# GA1A1S202WP-REV-B.net
KiCad netlist of a schematic drawn in EAGLE
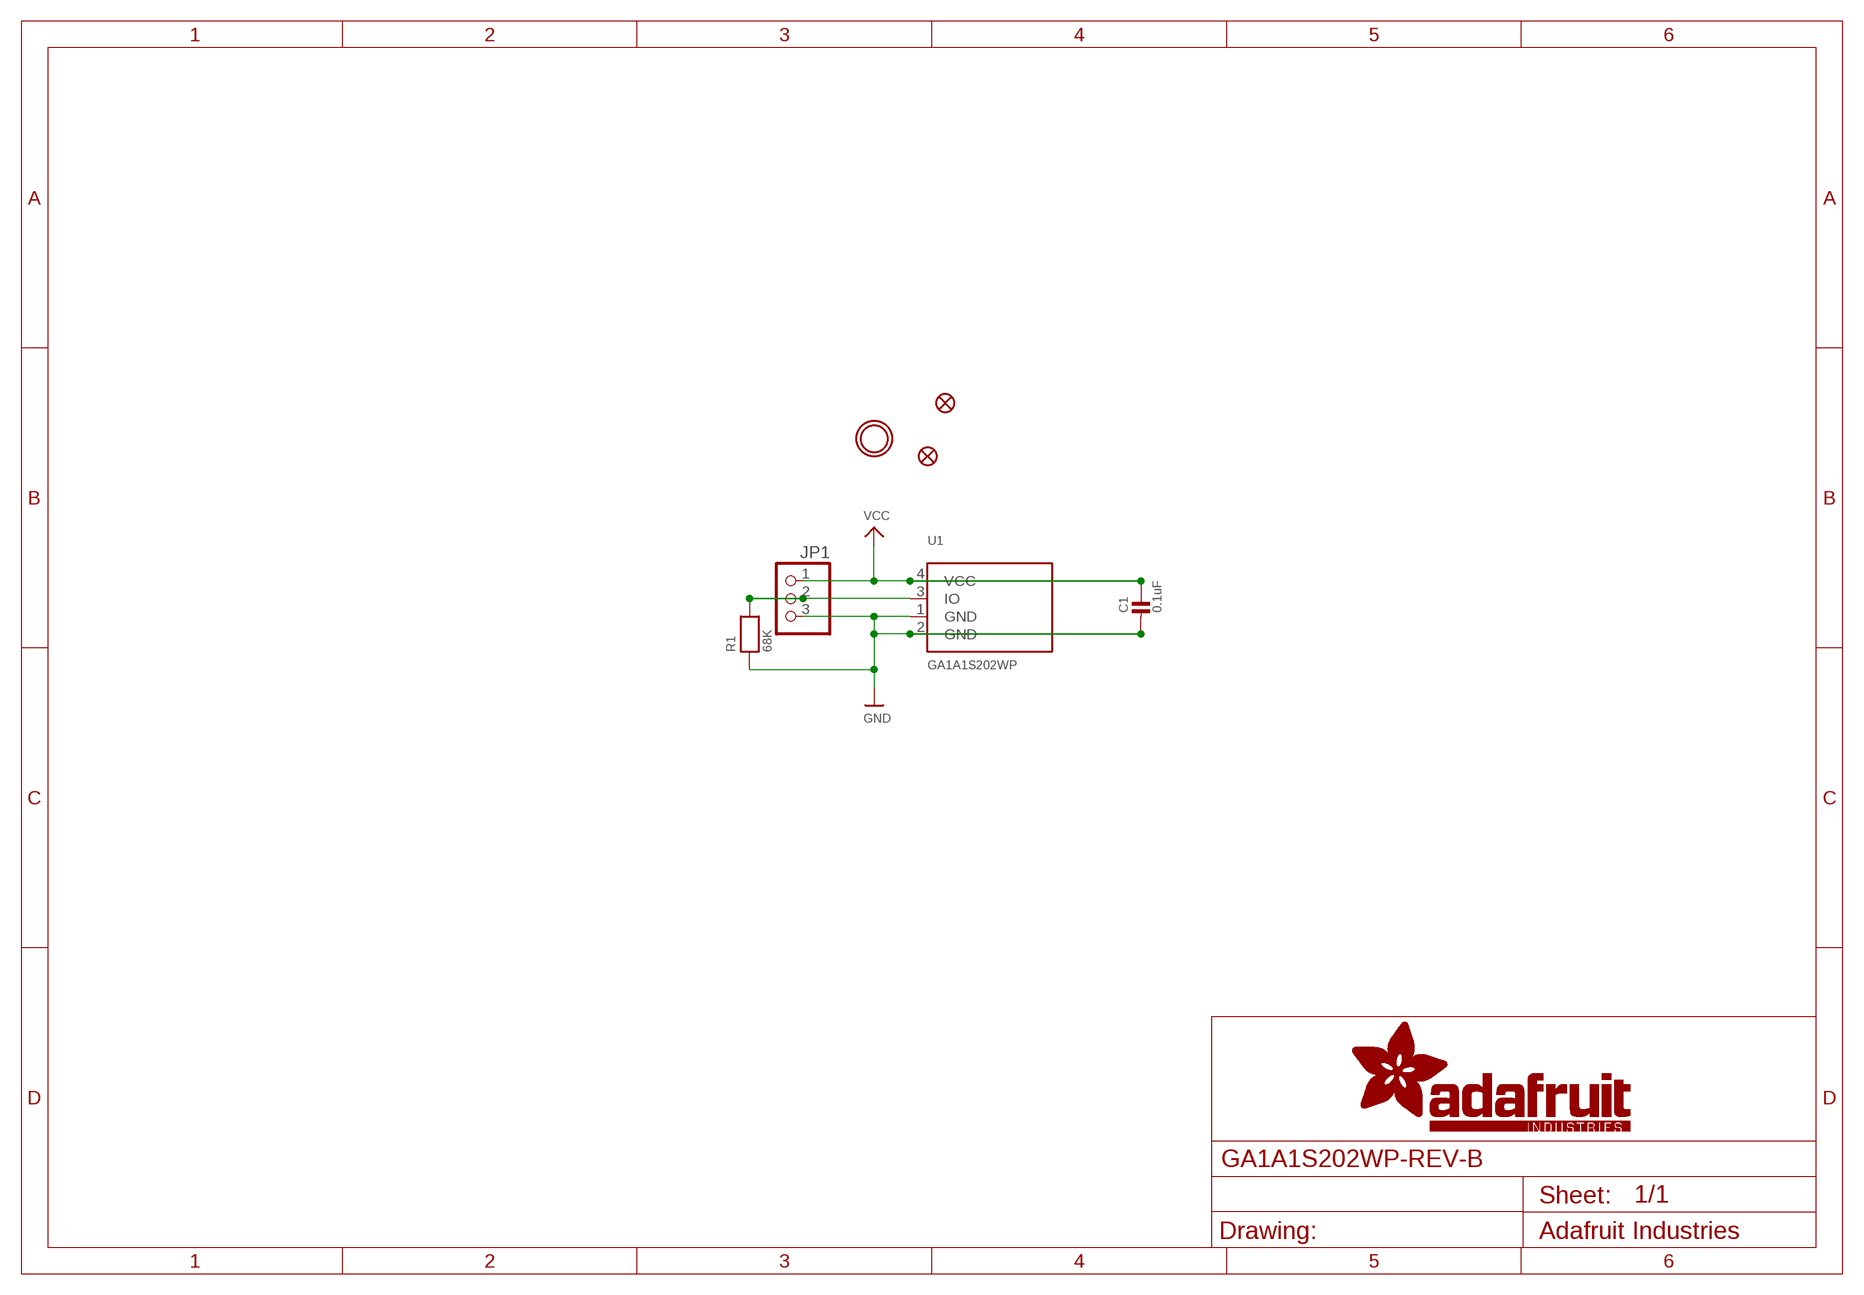
[diagram p0: schematic, sheet 1]

(export (version "E")
  (design (tool "Eeschema 10.0.6"))
  (components
    (comp (ref "C1")
      (value "0.1uF")
      (footprint "eagle-import:_0805MP")
      (libsource (lib "eagle-import") (part "CAP_CERAMIC_0805MP"))
    )
    (comp (ref "FID1")
      (value "FIDUCIAL\"\"")
      (footprint "eagle-import:FIDUCIAL_1MM")
      (libsource (lib "eagle-import") (part "FIDUCIAL{dblquote}{dblquote}"))
    )
    (comp (ref "FID2")
      (value "FIDUCIAL\"\"")
      (footprint "eagle-import:FIDUCIAL_1MM")
      (libsource (lib "eagle-import") (part "FIDUCIAL{dblquote}{dblquote}"))
    )
    (comp (ref "JP1")
      (value "HEADER-1X3ROUND")
      (footprint "eagle-import:1X03_ROUND")
      (libsource (lib "eagle-import") (part "HEADER-1X3ROUND"))
    )
    (comp (ref "R1")
      (value "68K")
      (footprint "eagle-import:_0805MP")
      (libsource (lib "eagle-import") (part "RESISTOR_0805MP"))
    )
    (comp (ref "U$3")
      (value "MOUNTINGHOLE2.5")
      (footprint "eagle-import:MOUNTINGHOLE_2.5_PLATED")
      (libsource (lib "eagle-import") (part "MOUNTINGHOLE2.5"))
    )
    (comp (ref "U1")
      (value "GA1A1S202WP")
      (footprint "eagle-import:GA1A1S202WP")
      (libsource (lib "eagle-import") (part "GA1A1S202WP"))
    )
  )
  (nets
    (net (code "1") (name "GND") (class "Default")
      (node (ref "C1") (pin "2") (pinfunction "P$2_2") (pintype "passive"))
      (node (ref "JP1") (pin "3") (pinfunction "3_3") (pintype "passive"))
      (node (ref "R1") (pin "1") (pinfunction "1_1") (pintype "passive"))
      (node (ref "U1") (pin "1") (pinfunction "GND_1") (pintype "power_in"))
      (node (ref "U1") (pin "2") (pinfunction "GND_2") (pintype "power_in"))
    )
    (net (code "2") (name "Net-(U1-IO)") (class "Default")
      (node (ref "JP1") (pin "2") (pinfunction "2_2") (pintype "passive"))
      (node (ref "R1") (pin "2") (pinfunction "2_2") (pintype "passive"))
      (node (ref "U1") (pin "3") (pinfunction "IO_3") (pintype "output"))
    )
    (net (code "3") (name "VCC") (class "Default")
      (node (ref "C1") (pin "1") (pinfunction "P$1_1") (pintype "passive"))
      (node (ref "JP1") (pin "1") (pinfunction "1_1") (pintype "passive"))
      (node (ref "U1") (pin "4") (pinfunction "VCC_4") (pintype "power_in"))
    )
  )
)
